# ST_LINK_V2-1.net
KiCad netlist of a schematic drawn in Altium Designer
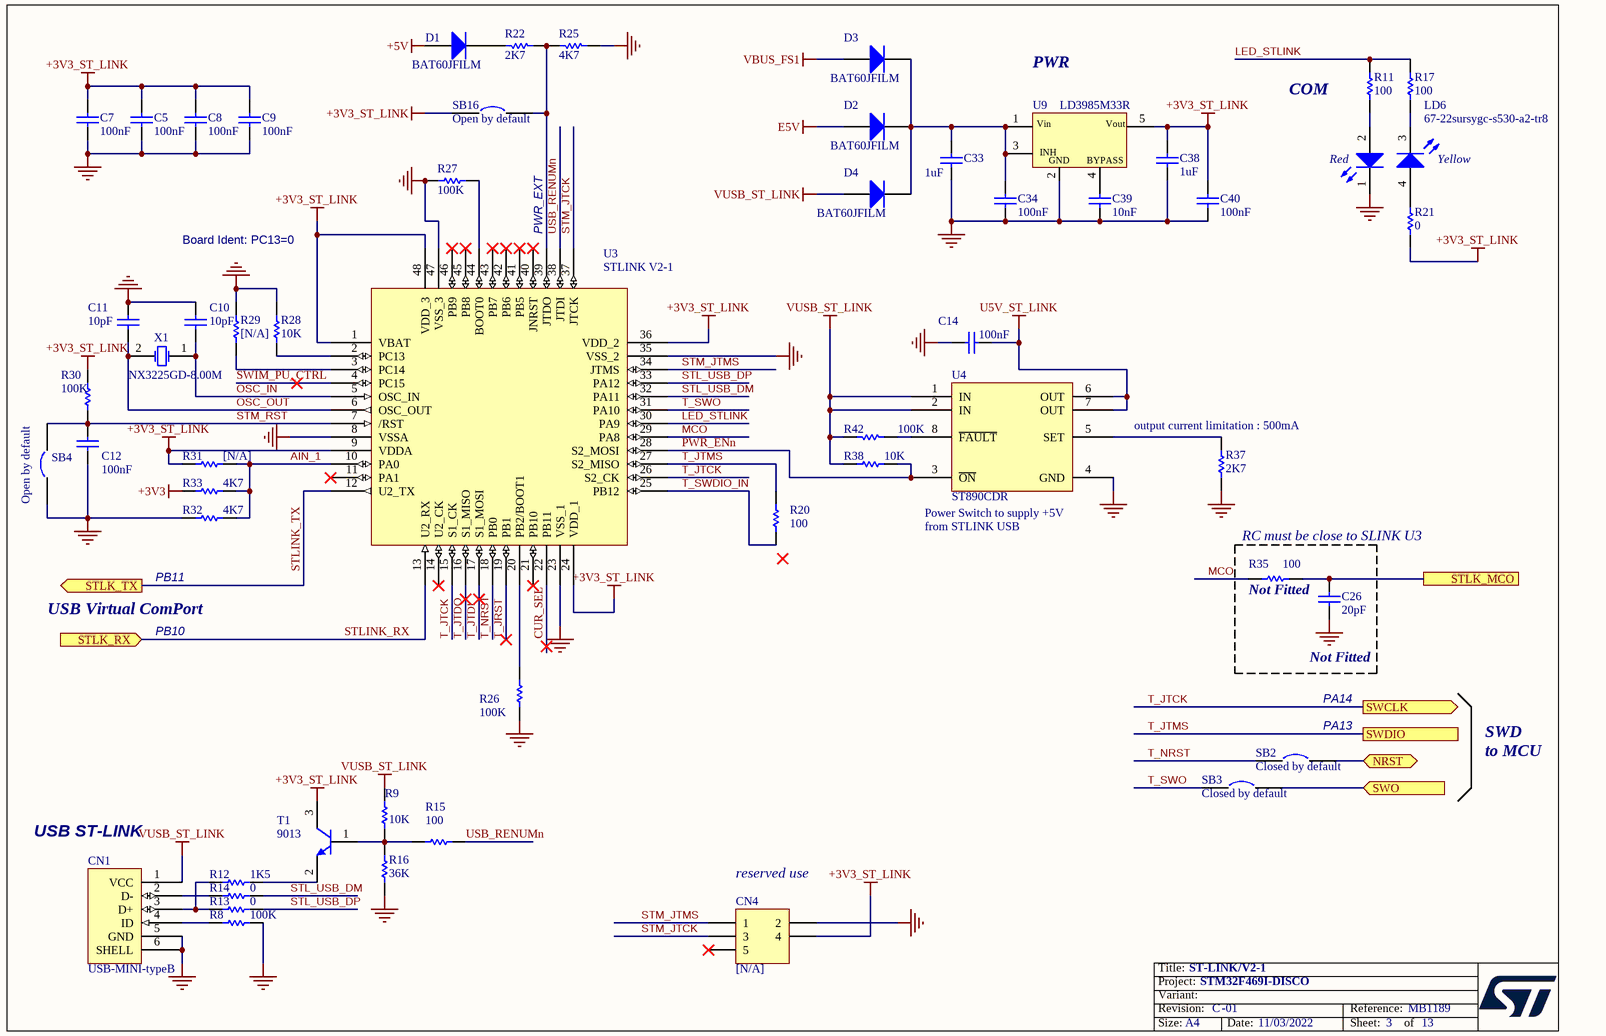
[diagram p0: ST_LINK_V2-1.SCHDOC]

(export (version "E")
  (design (tool "Eeschema 10.0.6"))
  (components
    (comp (ref "C5")
      (value "100nF")
      (footprint "0402C")
      (description "Capacitor 0402 / 0603 / 0805")
      (libsource (lib "MCD_TOOLS") (part "Capacitor_ST"))
    )
    (comp (ref "C7")
      (value "100nF")
      (footprint "0402C")
      (description "Capacitor 0402 / 0603 / 0805")
      (libsource (lib "MCD_TOOLS") (part "Capacitor_ST"))
    )
    (comp (ref "C8")
      (value "100nF")
      (footprint "0402C")
      (description "Capacitor 0402 / 0603 / 0805")
      (libsource (lib "MCD_TOOLS") (part "Capacitor_ST"))
    )
    (comp (ref "C9")
      (value "100nF")
      (footprint "0402C")
      (description "Capacitor 0402 / 0603 / 0805")
      (libsource (lib "MCD_TOOLS") (part "Capacitor_ST"))
    )
    (comp (ref "C10")
      (value "10pF")
      (footprint "0603C")
      (description "Capacitor 0402 / 0603 / 0805")
      (libsource (lib "MCD_TOOLS") (part "Capacitor_ST"))
    )
    (comp (ref "C11")
      (value "10pF")
      (footprint "0603C")
      (description "Capacitor 0402 / 0603 / 0805")
      (libsource (lib "MCD_TOOLS") (part "Capacitor_ST"))
    )
    (comp (ref "C12")
      (value "100nF")
      (footprint "0402C")
      (description "Capacitor 0402 / 0603 / 0805")
      (libsource (lib "MCD_TOOLS") (part "Capacitor_ST"))
    )
    (comp (ref "C14")
      (value "100nF")
      (footprint "0402C")
      (description "Capacitor 0402 / 0603 / 0805")
      (libsource (lib "MCD_TOOLS") (part "Capacitor_ST"))
    )
    (comp (ref "C26")
      (value "20pF")
      (footprint "0603C")
      (description "Capacitor,20pF,50V,NPO,5%,0402,YAGEO")
      (libsource (lib "MCD_TOOLS") (part "Cap_20pF_NPO_5%_0402"))
    )
    (comp (ref "C33")
      (value "1uF")
      (footprint "0603C")
      (description "Capacitor")
      (fields (field (name "TOLERANCE") "10%"))
      (libsource (lib "MB963_1") (part "CAP SMD 0603  X5R 1µF 25V 10%"))
    )
    (comp (ref "C34")
      (value "100nF")
      (footprint "0402C")
      (description "Capacitor 0402 / 0603 / 0805")
      (libsource (lib "MCD_TOOLS") (part "Capacitor_ST"))
    )
    (comp (ref "C38")
      (value "1uF")
      (footprint "0603C")
      (description "Capacitor")
      (fields (field (name "TOLERANCE") "10%"))
      (libsource (lib "MB963_1") (part "CAP SMD 0603  X5R 1µF 25V 10%"))
    )
    (comp (ref "C39")
      (value "10nF")
      (footprint "0603C")
      (description "0603  X7R 10NF")
      (fields (field (name "TOLERANCE") "10%"))
      (libsource (lib "MB963_1") (part "CAP SMD 0603  X7R 10000PF 50V 10%"))
    )
    (comp (ref "C40")
      (value "100nF")
      (footprint "0402C")
      (description "Capacitor 0402 / 0603 / 0805")
      (libsource (lib "MCD_TOOLS") (part "Capacitor_ST"))
    )
    (comp (ref "CN1")
      (value "USB-MINI-typeB")
      (footprint "MINIUSB_AB_5SM_RA")
      (description "USB-MINI-typeB connector")
      (libsource (lib "MCD_TOOLS") (part "USB-MINI-typeB connector"))
    )
    (comp (ref "CN4")
      (value "[N/A]")
      (footprint "HDR_2X3-1_2R54-6")
      (description "Header, 3-Pin, Dual row")
      (fields (field (name "PUBLISHER") "Altium Limited"))
      (libsource (lib "Miscellaneous Connectors") (part "Header 3X2"))
    )
    (comp (ref "D1")
      (value "BAT60JFILM")
      (footprint "SOD-323")
      (libsource (lib "MCD_TOOLS") (part "BAT60JFILM"))
    )
    (comp (ref "D2")
      (value "BAT60JFILM")
      (footprint "SOD-323")
      (libsource (lib "MCD_TOOLS") (part "BAT60JFILM"))
    )
    (comp (ref "D3")
      (value "BAT60JFILM")
      (footprint "SOD-323")
      (libsource (lib "MCD_TOOLS") (part "BAT60JFILM"))
    )
    (comp (ref "D4")
      (value "BAT60JFILM")
      (footprint "SOD-323")
      (libsource (lib "MCD_TOOLS") (part "BAT60JFILM"))
    )
    (comp (ref "LD6")
      (value "67-22sursygc-s530-a2-tr8")
      (footprint "LED2_3528")
      (libsource (lib "MB819") (part "HSMF-A201-A00J1"))
    )
    (comp (ref "R8")
      (value "100K")
      (footprint "0603R")
      (description "Resistor")
      (fields (field (name "PUBLISHER") "Altium Limited"))
      (libsource (lib "Miscellaneous Devices") (part "res1"))
    )
    (comp (ref "R9")
      (value "10K")
      (footprint "0402R")
      (description "Resistor")
      (fields (field (name "PUBLISHER") "Altium Limited"))
      (libsource (lib "") (part "Res1_2"))
    )
    (comp (ref "R11")
      (value "100")
      (footprint "0603R")
      (description "Resistor")
      (fields (field (name "PUBLISHER") "Altium Limited"))
      (libsource (lib "") (part "Res1_2"))
    )
    (comp (ref "R12")
      (value "1K5")
      (footprint "0603R")
      (description "Resistor")
      (libsource (lib "Miscellaneous Devices") (part "Res1"))
    )
    (comp (ref "R13")
      (value "0")
      (footprint "0603R")
      (description "Resistor")
      (libsource (lib "Miscellaneous Devices") (part "Res1"))
    )
    (comp (ref "R14")
      (value "0")
      (footprint "0603R")
      (description "Resistor")
      (libsource (lib "Miscellaneous Devices") (part "Res1"))
    )
    (comp (ref "R15")
      (value "100")
      (footprint "0603R")
      (description "Resistor 0402 / 0603 / 0805")
      (libsource (lib "Miscellaneous Devices") (part "Res1"))
    )
    (comp (ref "R16")
      (value "36K")
      (footprint "0603R")
      (description "Resistor")
      (fields (field (name "PUBLISHER") "Altium Limited"))
      (libsource (lib "") (part "Res1_2"))
    )
    (comp (ref "R17")
      (value "100")
      (footprint "0603R")
      (description "Resistor")
      (fields (field (name "PUBLISHER") "Altium Limited"))
      (libsource (lib "") (part "Res1_2"))
    )
    (comp (ref "R20")
      (value "100")
      (footprint "STM-SMEE:0603R")
      (description "Resistor")
      (libsource (lib "MCD_TOOLS") (part "Resistor_ST"))
    )
    (comp (ref "R21")
      (value "0")
      (footprint "0603R")
      (description "Resistor")
      (fields (field (name "PUBLISHER") "Altium Limited"))
      (libsource (lib "") (part "Res1_2"))
    )
    (comp (ref "R22")
      (value "2K7")
      (footprint "0603R")
      (description "Resistor")
      (fields (field (name "PUBLISHER") "Altium Limited"))
      (libsource (lib "") (part "Res1_1"))
    )
    (comp (ref "R25")
      (value "4K7")
      (footprint "0603R")
      (description "Resistor")
      (fields (field (name "PUBLISHER") "Altium Limited"))
      (libsource (lib "") (part "Res1_1"))
    )
    (comp (ref "R26")
      (value "100K")
      (footprint "0603R")
      (description "Resistor 0402 / 0603 / 0805")
      (libsource (lib "Miscellaneous Devices") (part "Res1"))
    )
    (comp (ref "R27")
      (value "100K")
      (footprint "0603R")
      (description "Resistor 0402 / 0603 / 0805")
      (libsource (lib "Miscellaneous Devices") (part "Res1"))
    )
    (comp (ref "R28")
      (value "10K")
      (footprint "0402R")
      (description "Resistor")
      (libsource (lib "Miscellaneous Devices") (part "Res1"))
    )
    (comp (ref "R29")
      (value "[N/A]")
      (footprint "0603R")
      (description "Resistor 0402 / 0603 / 0805")
      (libsource (lib "Miscellaneous Devices") (part "Res1"))
    )
    (comp (ref "R30")
      (value "100K")
      (footprint "0603R")
      (description "Resistor 0402 / 0603 / 0805")
      (libsource (lib "Miscellaneous Devices") (part "Res1"))
    )
    (comp (ref "R31")
      (value "[N/A]")
      (footprint "0603R")
      (description "Resistor 0402 / 0603 / 0805")
      (libsource (lib "Miscellaneous Devices") (part "Res1"))
    )
    (comp (ref "R32")
      (value "4K7")
      (footprint "0603R")
      (description "Resistor 0402 / 0603 / 0805")
      (libsource (lib "Miscellaneous Devices") (part "Res1"))
    )
    (comp (ref "R33")
      (value "4K7")
      (footprint "0603R")
      (description "Resistor 0402 / 0603 / 0805")
      (libsource (lib "Miscellaneous Devices") (part "Res1"))
    )
    (comp (ref "R35")
      (value "100")
      (footprint "0603R")
      (description "Resistor 0402 / 0603 / 0805")
      (libsource (lib "Miscellaneous Devices") (part "Res1"))
    )
    (comp (ref "R37")
      (value "2K7")
      (footprint "STM-SMEE:0603R")
      (description "Resistor 0402 / 0603 / 0805")
      (libsource (lib "MCD_TOOLS") (part "Resistor_ST"))
    )
    (comp (ref "R38")
      (value "10K")
      (footprint "0402R")
      (description "Resistor")
      (libsource (lib "MCD_TOOLS") (part "Resistor_ST"))
    )
    (comp (ref "R42")
      (value "100K")
      (footprint "0603R")
      (description "Resistor")
      (fields (field (name "PUBLISHER") "Altium Limited"))
      (libsource (lib "*") (part "Res1"))
    )
    (comp (ref "SB2")
      (value "Closed by default")
      (footprint "SB_0603")
      (description "Circuit Breaker")
      (fields (field (name "PUBLISHER") "Altium Limited"))
      (libsource (lib "Miscellaneous Devices") (part "Circuit Breaker"))
    )
    (comp (ref "SB3")
      (value "Closed by default")
      (footprint "SB_0603")
      (description "Circuit Breaker")
      (fields (field (name "PUBLISHER") "Altium Limited"))
      (libsource (lib "Miscellaneous Devices") (part "Circuit Breaker"))
    )
    (comp (ref "SB4")
      (value "Open by default")
      (footprint "SB_0603")
      (description "Circuit Breaker")
      (fields (field (name "PUBLISHER") "Altium Limited"))
      (libsource (lib "Miscellaneous Devices") (part "Circuit Breaker"))
    )
    (comp (ref "SB16")
      (value "Open by default")
      (footprint "SB_0603")
      (description "Circuit Breaker")
      (fields (field (name "PUBLISHER") "Altium Limited"))
      (libsource (lib "Miscellaneous Devices") (part "Circuit Breaker"))
    )
    (comp (ref "T1")
      (value "9013")
      (footprint "SOT-23")
      (description "NPN Bipolar Transistor")
      (fields (field (name "PUBLISHER") "Altium Limited"))
      (libsource (lib "MB1167") (part "NPN"))
    )
    (comp (ref "U3")
      (value "STLINK V2-1")
      (footprint "LQFP48_0R5_9X9")
      (libsource (lib "*") (part "STM32F10x(48pin)"))
    )
    (comp (ref "U4")
      (value "ST890CDR")
      (footprint "SOIC8_1R27_4R9X6")
      (libsource (lib "MB1167") (part "ST890CDR"))
    )
    (comp (ref "U9")
      (value "LD3985M33R")
      (footprint "SOT23-5")
      (description "Ultra low drop-low noise BiCMOS voltage, regulators low ESR capacitors compatible")
      (libsource (lib "MCD_TOOLS") (part "LD3985M33R"))
    )
    (comp (ref "X1")
      (value "NX3225GD-8.00M")
      (footprint "XTAL_2SM_3R2X2R5_H1")
      (description "Crystal 8Mhz, 8pF, -+50PPM, SMD")
      (libsource (lib "MCD_TOOLS") (part "XTAL_8M_NX3225GD"))
    )
  )
  (nets
    (net (code "1") (name "+3V3") (class "Default")
      (node (ref "R33") (pin "1") (pinfunction "1_1") (pintype "passive"))
    )
    (net (code "2") (name "+3V3_ST_LINK") (class "Default")
      (node (ref "C38") (pin "1") (pinfunction "1_1") (pintype "passive"))
      (node (ref "C40") (pin "2") (pinfunction "2_2") (pintype "passive"))
      (node (ref "C5") (pin "2") (pinfunction "2_2") (pintype "passive"))
      (node (ref "C7") (pin "2") (pinfunction "2_2") (pintype "passive"))
      (node (ref "C8") (pin "2") (pinfunction "2_2") (pintype "passive"))
      (node (ref "C9") (pin "2") (pinfunction "2_2") (pintype "passive"))
      (node (ref "CN4") (pin "4") (pinfunction "4_4") (pintype "passive"))
      (node (ref "R21") (pin "2") (pinfunction "2_2") (pintype "passive"))
      (node (ref "R30") (pin "2") (pinfunction "2_2") (pintype "passive"))
      (node (ref "R31") (pin "1") (pinfunction "1_1") (pintype "passive"))
      (node (ref "SB16") (pin "1") (pinfunction "1_1") (pintype "passive"))
      (node (ref "T1") (pin "3") (pinfunction "C_3") (pintype "passive"))
      (node (ref "U3") (pin "1") (pinfunction "VBAT_1") (pintype "power_in"))
      (node (ref "U3") (pin "24") (pinfunction "VDD_1_24") (pintype "power_in"))
      (node (ref "U3") (pin "36") (pinfunction "VDD_2_36") (pintype "power_in"))
      (node (ref "U3") (pin "48") (pinfunction "VDD_3_48") (pintype "power_in"))
      (node (ref "U3") (pin "9") (pinfunction "VDDA_9") (pintype "power_in"))
      (node (ref "U9") (pin "5") (pinfunction "Vout_5") (pintype "passive"))
    )
    (net (code "3") (name "+5V") (class "Default")
      (node (ref "D1") (pin "1") (pinfunction "A_1") (pintype "passive"))
    )
    (net (code "4") (name "/AIN_1") (class "Default")
      (node (ref "R31") (pin "2") (pinfunction "2_2") (pintype "passive"))
      (node (ref "R32") (pin "2") (pinfunction "2_2") (pintype "passive"))
      (node (ref "R33") (pin "2") (pinfunction "2_2") (pintype "passive"))
      (node (ref "U3") (pin "10") (pinfunction "PA0_10") (pintype "bidirectional"))
    )
    (net (code "5") (name "/CUR_SEL") (class "Default")
      (node (ref "U3") (pin "22") (pinfunction "PB11_22") (pintype "passive"))
    )
    (net (code "6") (name "/LED_STLINK") (class "Default")
      (node (ref "R11") (pin "1") (pinfunction "1_1") (pintype "passive"))
      (node (ref "R17") (pin "1") (pinfunction "1_1") (pintype "passive"))
      (node (ref "U3") (pin "30") (pinfunction "PA9_30") (pintype "bidirectional"))
    )
    (net (code "7") (name "/MCO") (class "Default")
      (node (ref "R35") (pin "1") (pinfunction "1_1") (pintype "passive"))
      (node (ref "U3") (pin "29") (pinfunction "PA8_29") (pintype "bidirectional"))
    )
    (net (code "8") (name "/NRST") (class "Default")
      (node (ref "SB2") (pin "2") (pinfunction "2_2") (pintype "passive"))
    )
    (net (code "9") (name "/OSC_IN") (class "Default")
      (node (ref "C10") (pin "1") (pinfunction "1_1") (pintype "passive"))
      (node (ref "U3") (pin "5") (pinfunction "OSC_IN_5") (pintype "input"))
      (node (ref "X1") (pin "1") (pinfunction "OSC1_1") (pintype "passive"))
    )
    (net (code "10") (name "/OSC_OUT") (class "Default")
      (node (ref "C11") (pin "1") (pinfunction "1_1") (pintype "passive"))
      (node (ref "U3") (pin "6") (pinfunction "OSC_OUT_6") (pintype "output"))
      (node (ref "X1") (pin "2") (pinfunction "OSC2_2") (pintype "passive"))
    )
    (net (code "11") (name "/PWR_ENn") (class "Default")
      (node (ref "R38") (pin "2") (pinfunction "2_2") (pintype "passive"))
      (node (ref "U3") (pin "28") (pinfunction "S2_MOSI_28") (pintype "bidirectional"))
      (node (ref "U4") (pin "3") (pinfunction "~{ON}_3") (pintype "passive"))
    )
    (net (code "12") (name "/STLINK_RX") (class "Default")
      (node (ref "U3") (pin "13") (pinfunction "U2_RX_13") (pintype "input"))
    )
    (net (code "13") (name "/STLINK_TX") (class "Default")
      (node (ref "U3") (pin "12") (pinfunction "U2_TX_12") (pintype "output"))
    )
    (net (code "14") (name "/STLK_MCO") (class "Default")
      (node (ref "C26") (pin "1") (pinfunction "1_1") (pintype "passive"))
      (node (ref "R35") (pin "2") (pinfunction "2_2") (pintype "passive"))
    )
    (net (code "15") (name "/STL_USB_DM") (class "Default")
      (node (ref "R14") (pin "2") (pinfunction "2_2") (pintype "passive"))
      (node (ref "U3") (pin "32") (pinfunction "PA11_32") (pintype "bidirectional"))
    )
    (net (code "16") (name "/STL_USB_DP") (class "Default")
      (node (ref "R13") (pin "2") (pinfunction "2_2") (pintype "passive"))
      (node (ref "U3") (pin "33") (pinfunction "PA12_33") (pintype "bidirectional"))
    )
    (net (code "17") (name "/STM_JTCK") (class "Default")
      (node (ref "CN4") (pin "3") (pinfunction "3_3") (pintype "passive"))
      (node (ref "U3") (pin "37") (pinfunction "JTCK_37") (pintype "bidirectional"))
    )
    (net (code "18") (name "/STM_JTMS") (class "Default")
      (node (ref "CN4") (pin "1") (pinfunction "1_1") (pintype "passive"))
      (node (ref "U3") (pin "34") (pinfunction "JTMS_34") (pintype "bidirectional"))
    )
    (net (code "19") (name "/STM_RST") (class "Default")
      (node (ref "C12") (pin "2") (pinfunction "2_2") (pintype "passive"))
      (node (ref "R30") (pin "1") (pinfunction "1_1") (pintype "passive"))
      (node (ref "SB4") (pin "2") (pinfunction "2_2") (pintype "passive"))
      (node (ref "U3") (pin "7") (pinfunction "/RST_7") (pintype "input"))
    )
    (net (code "20") (name "/SWIM_PU_CTRL") (class "Default")
      (node (ref "U3") (pin "4") (pinfunction "PC15_4") (pintype "bidirectional"))
    )
    (net (code "21") (name "/SWO") (class "Default")
      (node (ref "SB3") (pin "2") (pinfunction "2_2") (pintype "passive"))
    )
    (net (code "22") (name "/T_JRST") (class "Default")
      (node (ref "U3") (pin "19") (pinfunction "PB1_19") (pintype "bidirectional+no_connect"))
    )
    (net (code "23") (name "/T_JTCK") (class "Default")
      (node (ref "U3") (pin "15") (pinfunction "S1_CK_15") (pintype "bidirectional"))
      (node (ref "U3") (pin "26") (pinfunction "S2_CK_26") (pintype "bidirectional"))
    )
    (net (code "24") (name "/T_JTDI") (class "Default")
      (node (ref "U3") (pin "17") (pinfunction "S1_MOSI_17") (pintype "bidirectional"))
    )
    (net (code "25") (name "/T_JTDO") (class "Default")
      (node (ref "U3") (pin "16") (pinfunction "S1_MISO_16") (pintype "bidirectional"))
    )
    (net (code "26") (name "/T_JTMS") (class "Default")
      (node (ref "R20") (pin "2") (pinfunction "2_2") (pintype "passive"))
      (node (ref "U3") (pin "27") (pinfunction "S2_MISO_27") (pintype "bidirectional"))
    )
    (net (code "27") (name "/T_NRST") (class "Default")
      (node (ref "SB2") (pin "1") (pinfunction "1_1") (pintype "passive"))
      (node (ref "U3") (pin "18") (pinfunction "PB0_18") (pintype "bidirectional"))
    )
    (net (code "28") (name "/T_SWDIO_IN") (class "Default")
      (node (ref "R20") (pin "1") (pinfunction "1_1") (pintype "passive"))
      (node (ref "U3") (pin "25") (pinfunction "PB12_25") (pintype "bidirectional"))
    )
    (net (code "29") (name "/T_SWO") (class "Default")
      (node (ref "SB3") (pin "1") (pinfunction "1_1") (pintype "passive"))
      (node (ref "U3") (pin "31") (pinfunction "PA10_31") (pintype "bidirectional"))
    )
    (net (code "30") (name "/USB_RENUMn") (class "Default")
      (node (ref "R15") (pin "2") (pinfunction "2_2") (pintype "passive"))
      (node (ref "U3") (pin "38") (pinfunction "JTDI_38") (pintype "bidirectional"))
    )
    (net (code "31") (name "E5V") (class "Default")
      (node (ref "D2") (pin "1") (pinfunction "A_1") (pintype "passive"))
    )
    (net (code "32") (name "GND") (class "Default")
      (node (ref "C10") (pin "2") (pinfunction "2_2") (pintype "passive"))
      (node (ref "C11") (pin "2") (pinfunction "2_2") (pintype "passive"))
      (node (ref "C12") (pin "1") (pinfunction "1_1") (pintype "passive"))
      (node (ref "C14") (pin "1") (pinfunction "1_1") (pintype "passive"))
      (node (ref "C26") (pin "2") (pinfunction "2_2") (pintype "passive"))
      (node (ref "C33") (pin "1") (pinfunction "1_1") (pintype "passive"))
      (node (ref "C34") (pin "1") (pinfunction "1_1") (pintype "passive"))
      (node (ref "C38") (pin "2") (pinfunction "2_2") (pintype "passive"))
      (node (ref "C39") (pin "1") (pinfunction "1_1") (pintype "passive"))
      (node (ref "C40") (pin "1") (pinfunction "1_1") (pintype "passive"))
      (node (ref "C5") (pin "1") (pinfunction "1_1") (pintype "passive"))
      (node (ref "C7") (pin "1") (pinfunction "1_1") (pintype "passive"))
      (node (ref "C8") (pin "1") (pinfunction "1_1") (pintype "passive"))
      (node (ref "C9") (pin "1") (pinfunction "1_1") (pintype "passive"))
      (node (ref "CN1") (pin "5") (pinfunction "GND_5") (pintype "passive"))
      (node (ref "CN1") (pin "6") (pinfunction "SHELL_6") (pintype "passive"))
      (node (ref "CN4") (pin "2") (pinfunction "2_2") (pintype "passive"))
      (node (ref "LD6") (pin "1") (pinfunction "RED_cathode_1") (pintype "passive"))
      (node (ref "R16") (pin "1") (pinfunction "1_1") (pintype "passive"))
      (node (ref "R25") (pin "2") (pinfunction "2_2") (pintype "passive"))
      (node (ref "R26") (pin "1") (pinfunction "1_1") (pintype "passive"))
      (node (ref "R27") (pin "1") (pinfunction "1_1") (pintype "passive"))
      (node (ref "R28") (pin "1") (pinfunction "1_1") (pintype "passive"))
      (node (ref "R29") (pin "1") (pinfunction "1_1") (pintype "passive"))
      (node (ref "R32") (pin "1") (pinfunction "1_1") (pintype "passive"))
      (node (ref "R37") (pin "2") (pinfunction "2_2") (pintype "passive"))
      (node (ref "R8") (pin "2") (pinfunction "2_2") (pintype "passive"))
      (node (ref "SB4") (pin "1") (pinfunction "1_1") (pintype "passive"))
      (node (ref "U3") (pin "23") (pinfunction "VSS_1_23") (pintype "passive"))
      (node (ref "U3") (pin "35") (pinfunction "VSS_2_35") (pintype "passive"))
      (node (ref "U3") (pin "47") (pinfunction "VSS_3_47") (pintype "passive"))
      (node (ref "U3") (pin "8") (pinfunction "VSSA_8") (pintype "passive"))
      (node (ref "U4") (pin "4") (pinfunction "GND_4") (pintype "passive"))
      (node (ref "U9") (pin "2") (pinfunction "GND_2") (pintype "passive"))
    )
    (net (code "33") (name "Net-(CN1-D+)") (class "Default")
      (node (ref "CN1") (pin "3") (pinfunction "D+_3") (pintype "bidirectional"))
      (node (ref "R12") (pin "1") (pinfunction "1_1") (pintype "passive"))
      (node (ref "R13") (pin "1") (pinfunction "1_1") (pintype "passive"))
    )
    (net (code "34") (name "Net-(CN1-D-)") (class "Default")
      (node (ref "CN1") (pin "2") (pinfunction "D-_2") (pintype "bidirectional"))
      (node (ref "R14") (pin "1") (pinfunction "1_1") (pintype "passive"))
    )
    (net (code "35") (name "Net-(CN1-ID)") (class "Default")
      (node (ref "CN1") (pin "4") (pinfunction "ID_4") (pintype "input"))
      (node (ref "R8") (pin "1") (pinfunction "1_1") (pintype "passive"))
    )
    (net (code "36") (name "Net-(D1-K)") (class "Default")
      (node (ref "D1") (pin "2") (pinfunction "K_2") (pintype "passive"))
      (node (ref "R22") (pin "1") (pinfunction "1_1") (pintype "passive"))
    )
    (net (code "37") (name "Net-(D2-K)") (class "Default")
      (node (ref "C33") (pin "2") (pinfunction "2_2") (pintype "passive"))
      (node (ref "C34") (pin "2") (pinfunction "2_2") (pintype "passive"))
      (node (ref "D2") (pin "2") (pinfunction "K_2") (pintype "passive"))
      (node (ref "D3") (pin "2") (pinfunction "K_2") (pintype "passive"))
      (node (ref "D4") (pin "2") (pinfunction "K_2") (pintype "passive"))
      (node (ref "U9") (pin "1") (pinfunction "Vin_1") (pintype "passive"))
      (node (ref "U9") (pin "3") (pinfunction "CE_3") (pintype "passive"))
    )
    (net (code "38") (name "Net-(LD6-Red_anode)") (class "Default")
      (node (ref "LD6") (pin "2") (pinfunction "Red_anode_2") (pintype "passive"))
      (node (ref "R11") (pin "2") (pinfunction "2_2") (pintype "passive"))
    )
    (net (code "39") (name "Net-(LD6-YellowGreen_anode)") (class "Default")
      (node (ref "LD6") (pin "4") (pinfunction "YellowGreen_anode_4") (pintype "passive"))
      (node (ref "R21") (pin "1") (pinfunction "1_1") (pintype "passive"))
    )
    (net (code "40") (name "Net-(LD6-YellowGreen_cathode)") (class "Default")
      (node (ref "LD6") (pin "3") (pinfunction "YellowGreen_cathode_3") (pintype "passive"))
      (node (ref "R17") (pin "2") (pinfunction "2_2") (pintype "passive"))
    )
    (net (code "41") (name "Net-(T1-B)") (class "Default")
      (node (ref "R15") (pin "1") (pinfunction "1_1") (pintype "passive"))
      (node (ref "R16") (pin "2") (pinfunction "2_2") (pintype "passive"))
      (node (ref "R9") (pin "1") (pinfunction "1_1") (pintype "passive"))
      (node (ref "T1") (pin "1") (pinfunction "B_1") (pintype "passive"))
    )
    (net (code "42") (name "Net-(T1-E)") (class "Default")
      (node (ref "R12") (pin "2") (pinfunction "2_2") (pintype "passive"))
      (node (ref "T1") (pin "2") (pinfunction "E_2") (pintype "passive"))
    )
    (net (code "43") (name "Net-(U3-BOOT0)") (class "Default")
      (node (ref "R27") (pin "2") (pinfunction "2_2") (pintype "passive"))
      (node (ref "U3") (pin "44") (pinfunction "BOOT0_44") (pintype "bidirectional"))
    )
    (net (code "44") (name "Net-(U3-JTDO)") (class "Default")
      (node (ref "R22") (pin "2") (pinfunction "2_2") (pintype "passive"))
      (node (ref "R25") (pin "1") (pinfunction "1_1") (pintype "passive"))
      (node (ref "SB16") (pin "2") (pinfunction "2_2") (pintype "passive"))
      (node (ref "U3") (pin "39") (pinfunction "JTDO_39") (pintype "bidirectional"))
    )
    (net (code "45") (name "Net-(U3-PB2{slash}BOOT1)") (class "Default")
      (node (ref "R26") (pin "2") (pinfunction "2_2") (pintype "passive"))
      (node (ref "U3") (pin "20") (pinfunction "PB2/BOOT1_20") (pintype "passive"))
    )
    (net (code "46") (name "Net-(U3-PC13)") (class "Default")
      (node (ref "R28") (pin "2") (pinfunction "2_2") (pintype "passive"))
      (node (ref "U3") (pin "2") (pinfunction "PC13_2") (pintype "bidirectional"))
    )
    (net (code "47") (name "Net-(U3-PC14)") (class "Default")
      (node (ref "R29") (pin "2") (pinfunction "2_2") (pintype "passive"))
      (node (ref "U3") (pin "3") (pinfunction "PC14_3") (pintype "bidirectional"))
    )
    (net (code "48") (name "Net-(U4-SET)") (class "Default")
      (node (ref "R37") (pin "1") (pinfunction "1_1") (pintype "passive"))
      (node (ref "U4") (pin "5") (pinfunction "SET_5") (pintype "passive"))
    )
    (net (code "49") (name "Net-(U4-~{FAULT})") (class "Default")
      (node (ref "R42") (pin "2") (pinfunction "2_2") (pintype "passive"))
      (node (ref "U4") (pin "8") (pinfunction "~{FAULT}_8") (pintype "passive"))
    )
    (net (code "50") (name "Net-(U9-BYPASS)") (class "Default")
      (node (ref "C39") (pin "2") (pinfunction "2_2") (pintype "passive"))
      (node (ref "U9") (pin "4") (pinfunction "BYPASS_4") (pintype "passive"))
    )
    (net (code "51") (name "U5V_ST_LINK") (class "Default")
      (node (ref "C14") (pin "2") (pinfunction "2_2") (pintype "passive"))
      (node (ref "U4") (pin "6") (pinfunction "OUT_6") (pintype "passive"))
      (node (ref "U4") (pin "7") (pinfunction "OUT_7") (pintype "passive"))
    )
    (net (code "52") (name "VBUS_FS1") (class "Default")
      (node (ref "D3") (pin "1") (pinfunction "A_1") (pintype "passive"))
    )
    (net (code "53") (name "VUSB_ST_LINK") (class "Default")
      (node (ref "CN1") (pin "1") (pinfunction "VCC_1") (pintype "power_in"))
      (node (ref "D4") (pin "1") (pinfunction "A_1") (pintype "passive"))
      (node (ref "R38") (pin "1") (pinfunction "1_1") (pintype "passive"))
      (node (ref "R42") (pin "1") (pinfunction "1_1") (pintype "passive"))
      (node (ref "R9") (pin "2") (pinfunction "2_2") (pintype "passive"))
      (node (ref "U4") (pin "1") (pinfunction "IN_1") (pintype "passive"))
      (node (ref "U4") (pin "2") (pinfunction "IN_2") (pintype "passive"))
    )
    (net (code "54") (name "unconnected-(CN4-Pad5)") (class "Default")
      (node (ref "CN4") (pin "5") (pinfunction "5_5") (pintype "passive+no_connect"))
    )
    (net (code "55") (name "unconnected-(U3-JNRST-Pad40)") (class "Default")
      (node (ref "U3") (pin "40") (pinfunction "JNRST_40") (pintype "bidirectional+no_connect"))
    )
    (net (code "56") (name "unconnected-(U3-PA1-Pad11)") (class "Default")
      (node (ref "U3") (pin "11") (pinfunction "PA1_11") (pintype "bidirectional+no_connect"))
    )
    (net (code "57") (name "unconnected-(U3-PB5-Pad41)") (class "Default")
      (node (ref "U3") (pin "41") (pinfunction "PB5_41") (pintype "bidirectional+no_connect"))
    )
    (net (code "58") (name "unconnected-(U3-PB6-Pad42)") (class "Default")
      (node (ref "U3") (pin "42") (pinfunction "PB6_42") (pintype "bidirectional+no_connect"))
    )
    (net (code "59") (name "unconnected-(U3-PB7-Pad43)") (class "Default")
      (node (ref "U3") (pin "43") (pinfunction "PB7_43") (pintype "bidirectional+no_connect"))
    )
    (net (code "60") (name "unconnected-(U3-PB8-Pad45)") (class "Default")
      (node (ref "U3") (pin "45") (pinfunction "PB8_45") (pintype "bidirectional+no_connect"))
    )
    (net (code "61") (name "unconnected-(U3-PB9-Pad46)") (class "Default")
      (node (ref "U3") (pin "46") (pinfunction "PB9_46") (pintype "bidirectional+no_connect"))
    )
    (net (code "62") (name "unconnected-(U3-PB10-Pad21)") (class "Default")
      (node (ref "U3") (pin "21") (pinfunction "PB10_21") (pintype "bidirectional+no_connect"))
    )
    (net (code "63") (name "unconnected-(U3-U2_CK-Pad14)") (class "Default")
      (node (ref "U3") (pin "14") (pinfunction "U2_CK_14") (pintype "bidirectional+no_connect"))
    )
  )
)
